# key.net
KiCad netlist of a schematic drawn in EAGLE
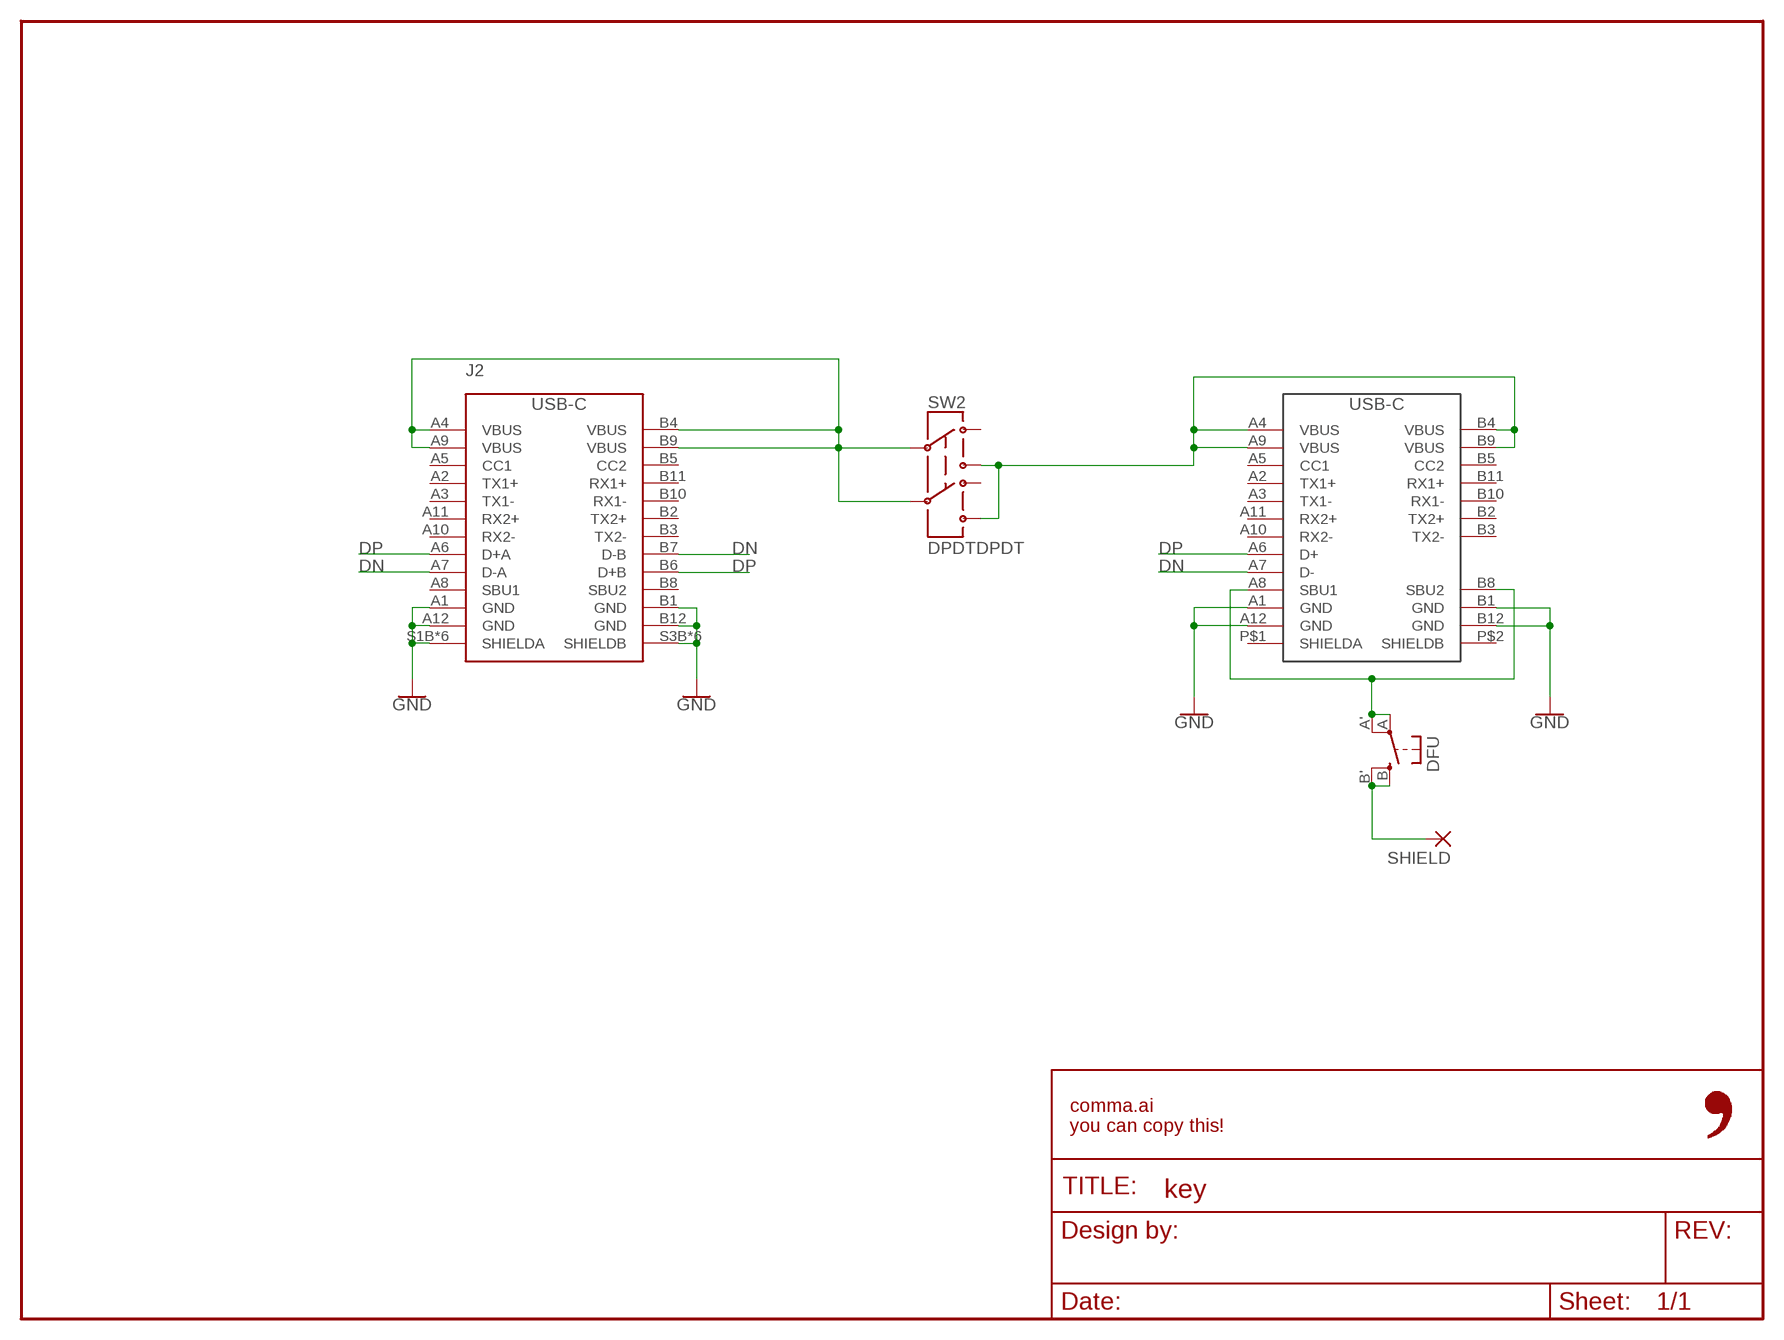
[diagram p0: schematic, sheet 1]

(export (version "E")
  (design (tool "Eeschema 10.0.6"))
  (components
    (comp (ref "DFU")
      (value "SPST-2-4PIN")
      (footprint "eagle-import:EVQ-Q2")
      (fields (field (name "MPN") "EVQ-Q2Y03W"))
      (libsource (lib "eagle-import") (part "SPST-2-4PIN"))
    )
    (comp (ref "FRAME1")
      (value "FRAME-LETTER-OPENNO_PACKAGE")
      (footprint "eagle-import:DUMMY")
      (fields (field (name "DESIGNER") "Nobody"))
      (libsource (lib "eagle-import") (part "FRAME-LETTER-OPENNO_PACKAGE"))
    )
    (comp (ref "J1")
      (value "USB-C")
      (footprint "eagle-import:USB-C")
      (fields (field (name "MPN") "10544440001"))
      (libsource (lib "eagle-import") (part "USB-C"))
    )
    (comp (ref "J2")
      (value "USB-C-FEMALE")
      (footprint "eagle-import:DX07S024XJ1R1100")
      (fields (field (name "MPN") "DX07S024XJ1R1100"))
      (libsource (lib "eagle-import") (part "USB-C-FEMALE"))
    )
    (comp (ref "SHIELD")
      (value "1,6/0,8")
      (footprint "eagle-import:1,6_0,8")
      (libsource (lib "eagle-import") (part "1,6/0,8"))
    )
    (comp (ref "SW2")
      (value "DPDTDPDT")
      (footprint "eagle-import:AYZ0202")
      (fields (field (name "MPN") "JS202011SCQN"))
      (libsource (lib "eagle-import") (part "DPDTDPDT"))
    )
  )
  (nets
    (net (code "1") (name "/DN") (class "Default")
      (node (ref "J1") (pin "A7") (pinfunction "D-_A7") (pintype "bidirectional"))
      (node (ref "J2") (pin "A7") (pinfunction "D-A_A7") (pintype "bidirectional"))
      (node (ref "J2") (pin "B7") (pinfunction "D-B_B7") (pintype "bidirectional"))
    )
    (net (code "2") (name "/DP") (class "Default")
      (node (ref "J1") (pin "A6") (pinfunction "D+_A6") (pintype "bidirectional"))
      (node (ref "J2") (pin "A6") (pinfunction "D+A_A6") (pintype "bidirectional"))
      (node (ref "J2") (pin "B6") (pinfunction "D+B_B6") (pintype "bidirectional"))
    )
    (net (code "3") (name "GND") (class "Default")
      (node (ref "J1") (pin "A1") (pinfunction "GND_A1") (pintype "bidirectional"))
      (node (ref "J1") (pin "A12") (pinfunction "GND_A12") (pintype "bidirectional"))
      (node (ref "J1") (pin "B1") (pinfunction "GND_B1") (pintype "bidirectional"))
      (node (ref "J1") (pin "B12") (pinfunction "GND_B12") (pintype "bidirectional"))
      (node (ref "J2") (pin "A1") (pinfunction "GND_A1") (pintype "bidirectional"))
      (node (ref "J2") (pin "A12") (pinfunction "GND_A12") (pintype "bidirectional"))
      (node (ref "J2") (pin "B1") (pinfunction "GND_B1") (pintype "bidirectional"))
      (node (ref "J2") (pin "B12") (pinfunction "GND_B12") (pintype "bidirectional"))
      (node (ref "J2") (pin "S1B") (pinfunction "SHIELDA_S1B") (pintype "bidirectional"))
      (node (ref "J2") (pin "S1T") (pinfunction "SHIELDA_S1T") (pintype "bidirectional"))
      (node (ref "J2") (pin "S1TH") (pinfunction "SHIELDA_S1TH") (pintype "bidirectional"))
      (node (ref "J2") (pin "S2B") (pinfunction "SHIELDA_S2B") (pintype "bidirectional"))
      (node (ref "J2") (pin "S2T") (pinfunction "SHIELDA_S2T") (pintype "bidirectional"))
      (node (ref "J2") (pin "S2TH") (pinfunction "SHIELDA_S2TH") (pintype "bidirectional"))
      (node (ref "J2") (pin "S3B") (pinfunction "SHIELDB_S3B") (pintype "bidirectional"))
      (node (ref "J2") (pin "S3T") (pinfunction "SHIELDB_S3T") (pintype "bidirectional"))
      (node (ref "J2") (pin "S3TH") (pinfunction "SHIELDB_S3TH") (pintype "bidirectional"))
      (node (ref "J2") (pin "S4B") (pinfunction "SHIELDB_S4B") (pintype "bidirectional"))
      (node (ref "J2") (pin "S4T") (pinfunction "SHIELDB_S4T") (pintype "bidirectional"))
      (node (ref "J2") (pin "S4TH") (pinfunction "SHIELDB_S4TH") (pintype "bidirectional"))
    )
    (net (code "4") (name "Net-(DFU-P)") (class "Default")
      (node (ref "DFU") (pin "A") (pinfunction "P_A") (pintype "passive"))
      (node (ref "DFU") (pin "A'") (pinfunction "P1_A'") (pintype "passive"))
      (node (ref "J1") (pin "A8") (pinfunction "SBU1_A8") (pintype "bidirectional"))
      (node (ref "J1") (pin "B8") (pinfunction "SBU2_B8") (pintype "bidirectional"))
    )
    (net (code "5") (name "Net-(DFU-S)") (class "Default")
      (node (ref "DFU") (pin "B") (pinfunction "S_B") (pintype "passive"))
      (node (ref "DFU") (pin "B'") (pinfunction "S1_B'") (pintype "passive"))
      (node (ref "SHIELD") (pin "1") (pinfunction "P_1") (pintype "passive"))
    )
    (net (code "6") (name "Net-(J1-VBUS-PadA4)") (class "Default")
      (node (ref "J1") (pin "A4") (pinfunction "VBUS_A4") (pintype "bidirectional"))
      (node (ref "J1") (pin "A9") (pinfunction "VBUS_A9") (pintype "bidirectional"))
      (node (ref "J1") (pin "B4") (pinfunction "VBUS_B4") (pintype "bidirectional"))
      (node (ref "J1") (pin "B9") (pinfunction "VBUS_B9") (pintype "bidirectional"))
      (node (ref "SW2") (pin "3") (pinfunction "3_3") (pintype "bidirectional"))
      (node (ref "SW2") (pin "6") (pinfunction "6_6") (pintype "bidirectional"))
    )
    (net (code "7") (name "Net-(J2-VBUS-PadA4)") (class "Default")
      (node (ref "J2") (pin "A4") (pinfunction "VBUS_A4") (pintype "bidirectional"))
      (node (ref "J2") (pin "A9") (pinfunction "VBUS_A9") (pintype "bidirectional"))
      (node (ref "J2") (pin "B4") (pinfunction "VBUS_B4") (pintype "bidirectional"))
      (node (ref "J2") (pin "B9") (pinfunction "VBUS_B9") (pintype "bidirectional"))
      (node (ref "SW2") (pin "2") (pinfunction "2_2") (pintype "bidirectional"))
      (node (ref "SW2") (pin "5") (pinfunction "5_5") (pintype "bidirectional"))
    )
    (net (code "8") (name "unconnected-(J1-CC1-PadA5)") (class "Default")
      (node (ref "J1") (pin "A5") (pinfunction "CC1_A5") (pintype "bidirectional"))
    )
    (net (code "9") (name "unconnected-(J1-CC2-PadB5)") (class "Default")
      (node (ref "J1") (pin "B5") (pinfunction "CC2_B5") (pintype "bidirectional"))
    )
    (net (code "10") (name "unconnected-(J1-RX1+-PadB11)") (class "Default")
      (node (ref "J1") (pin "B11") (pinfunction "RX1+_B11") (pintype "bidirectional"))
    )
    (net (code "11") (name "unconnected-(J1-RX1--PadB10)") (class "Default")
      (node (ref "J1") (pin "B10") (pinfunction "RX1-_B10") (pintype "bidirectional"))
    )
    (net (code "12") (name "unconnected-(J1-RX2+-PadA11)") (class "Default")
      (node (ref "J1") (pin "A11") (pinfunction "RX2+_A11") (pintype "bidirectional"))
    )
    (net (code "13") (name "unconnected-(J1-RX2--PadA10)") (class "Default")
      (node (ref "J1") (pin "A10") (pinfunction "RX2-_A10") (pintype "bidirectional"))
    )
    (net (code "14") (name "unconnected-(J1-SHIELDA-PadP$1)") (class "Default")
      (node (ref "J1") (pin "P$1") (pinfunction "SHIELDA_P$1") (pintype "bidirectional"))
    )
    (net (code "15") (name "unconnected-(J1-SHIELDB-PadP$2)") (class "Default")
      (node (ref "J1") (pin "P$2") (pinfunction "SHIELDB_P$2") (pintype "bidirectional"))
    )
    (net (code "16") (name "unconnected-(J1-TX1+-PadA2)") (class "Default")
      (node (ref "J1") (pin "A2") (pinfunction "TX1+_A2") (pintype "bidirectional"))
    )
    (net (code "17") (name "unconnected-(J1-TX1--PadA3)") (class "Default")
      (node (ref "J1") (pin "A3") (pinfunction "TX1-_A3") (pintype "bidirectional"))
    )
    (net (code "18") (name "unconnected-(J1-TX2+-PadB2)") (class "Default")
      (node (ref "J1") (pin "B2") (pinfunction "TX2+_B2") (pintype "bidirectional"))
    )
    (net (code "19") (name "unconnected-(J1-TX2--PadB3)") (class "Default")
      (node (ref "J1") (pin "B3") (pinfunction "TX2-_B3") (pintype "bidirectional"))
    )
    (net (code "20") (name "unconnected-(J2-CC1-PadA5)") (class "Default")
      (node (ref "J2") (pin "A5") (pinfunction "CC1_A5") (pintype "bidirectional"))
    )
    (net (code "21") (name "unconnected-(J2-CC2-PadB5)") (class "Default")
      (node (ref "J2") (pin "B5") (pinfunction "CC2_B5") (pintype "bidirectional"))
    )
    (net (code "22") (name "unconnected-(J2-RX1+-PadB11)") (class "Default")
      (node (ref "J2") (pin "B11") (pinfunction "RX1+_B11") (pintype "bidirectional"))
    )
    (net (code "23") (name "unconnected-(J2-RX1--PadB10)") (class "Default")
      (node (ref "J2") (pin "B10") (pinfunction "RX1-_B10") (pintype "bidirectional"))
    )
    (net (code "24") (name "unconnected-(J2-RX2+-PadA11)") (class "Default")
      (node (ref "J2") (pin "A11") (pinfunction "RX2+_A11") (pintype "bidirectional"))
    )
    (net (code "25") (name "unconnected-(J2-RX2--PadA10)") (class "Default")
      (node (ref "J2") (pin "A10") (pinfunction "RX2-_A10") (pintype "bidirectional"))
    )
    (net (code "26") (name "unconnected-(J2-SBU1-PadA8)") (class "Default")
      (node (ref "J2") (pin "A8") (pinfunction "SBU1_A8") (pintype "bidirectional"))
    )
    (net (code "27") (name "unconnected-(J2-SBU2-PadB8)") (class "Default")
      (node (ref "J2") (pin "B8") (pinfunction "SBU2_B8") (pintype "bidirectional"))
    )
    (net (code "28") (name "unconnected-(J2-TX1+-PadA2)") (class "Default")
      (node (ref "J2") (pin "A2") (pinfunction "TX1+_A2") (pintype "bidirectional"))
    )
    (net (code "29") (name "unconnected-(J2-TX1--PadA3)") (class "Default")
      (node (ref "J2") (pin "A3") (pinfunction "TX1-_A3") (pintype "bidirectional"))
    )
    (net (code "30") (name "unconnected-(J2-TX2+-PadB2)") (class "Default")
      (node (ref "J2") (pin "B2") (pinfunction "TX2+_B2") (pintype "bidirectional"))
    )
    (net (code "31") (name "unconnected-(J2-TX2--PadB3)") (class "Default")
      (node (ref "J2") (pin "B3") (pinfunction "TX2-_B3") (pintype "bidirectional"))
    )
    (net (code "32") (name "unconnected-(SW2-Pad1)") (class "Default")
      (node (ref "SW2") (pin "1") (pinfunction "1_1") (pintype "bidirectional"))
    )
    (net (code "33") (name "unconnected-(SW2-Pad4)") (class "Default")
      (node (ref "SW2") (pin "4") (pinfunction "4_4") (pintype "bidirectional"))
    )
  )
)
